# M2k_ADG_multiplexer_board.net
KiCad netlist of a schematic drawn in EAGLE
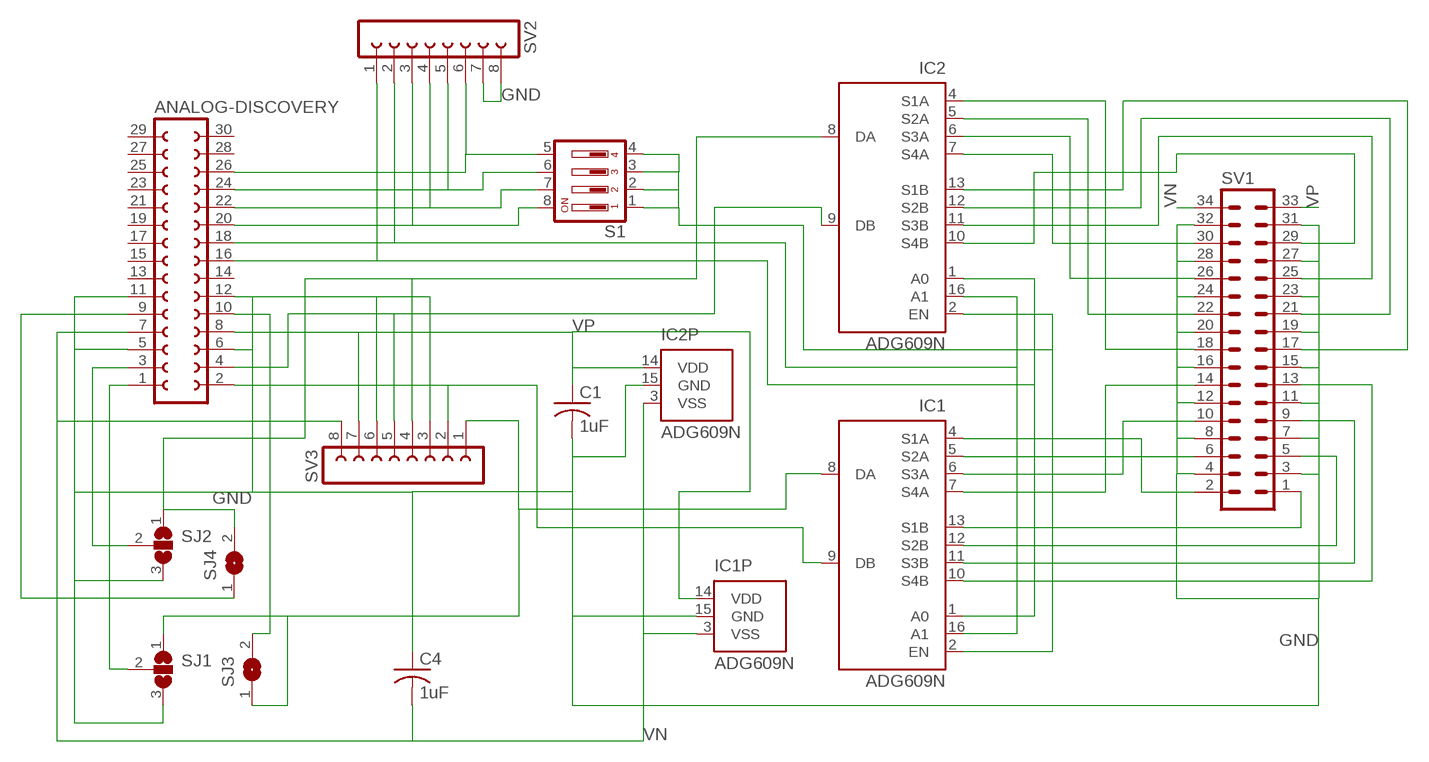
[diagram p0: schematic, sheet 1]

(export (version "E")
  (design (tool "Eeschema 10.0.6"))
  (components
    (comp (ref "ANALOG-DISCOVERY")
      (value "FE15-2")
      (footprint "eagle-import:FE15-2")
      (libsource (lib "eagle-import") (part "FE15-2"))
    )
    (comp (ref "C1")
      (value "1uF")
      (footprint "eagle-import:C050-024X044")
      (libsource (lib "eagle-import") (part "C-US050-024X044"))
    )
    (comp (ref "C4")
      (value "1uF")
      (footprint "eagle-import:C050-024X044")
      (libsource (lib "eagle-import") (part "C-US050-024X044"))
    )
    (comp (ref "IC1")
      (value "ADG609N")
      (footprint "eagle-import:DIL16")
      (fields (field (name "MF") "ALTERA CORPORATION") (field (name "MPN") "ADG609BN"))
      (libsource (lib "eagle-import") (part "ADG609N"))
    )
    (comp (ref "IC2")
      (value "ADG609N")
      (footprint "eagle-import:DIL16")
      (fields (field (name "MF") "ALTERA CORPORATION") (field (name "MPN") "ADG609BN"))
      (libsource (lib "eagle-import") (part "ADG609N"))
    )
    (comp (ref "S1")
      (value "DIP04YL")
      (footprint "eagle-import:DIP04YL")
      (libsource (lib "eagle-import") (part "DIP04YL"))
    )
    (comp (ref "SJ1")
      (value "SJ2W")
      (footprint "eagle-import:SJ_2")
      (libsource (lib "eagle-import") (part "SJ2W"))
    )
    (comp (ref "SJ2")
      (value "SJ2W")
      (footprint "eagle-import:SJ_2")
      (libsource (lib "eagle-import") (part "SJ2W"))
    )
    (comp (ref "SJ3") (value "SJ") (footprint "eagle-import:SJ") (libsource (lib "eagle-import") (part "SJ")))
    (comp (ref "SJ4") (value "SJ") (footprint "eagle-import:SJ") (libsource (lib "eagle-import") (part "SJ")))
    (comp (ref "SV1")
      (value "MA17-2")
      (footprint "eagle-import:MA17-2")
      (libsource (lib "eagle-import") (part "MA17-2"))
    )
    (comp (ref "SV2")
      (value "FE08-1")
      (footprint "eagle-import:FE08")
      (libsource (lib "eagle-import") (part "FE08-1"))
    )
    (comp (ref "SV3")
      (value "FE08-1")
      (footprint "eagle-import:FE08")
      (libsource (lib "eagle-import") (part "FE08-1"))
    )
  )
  (nets
    (net (code "1") (name "/GND") (class "Default")
      (node (ref "ANALOG-DISCOVERY") (pin "11") (pinfunction "11_11") (pintype "passive"))
      (node (ref "ANALOG-DISCOVERY") (pin "12") (pinfunction "12_12") (pintype "passive"))
      (node (ref "ANALOG-DISCOVERY") (pin "5") (pinfunction "5_5") (pintype "passive"))
      (node (ref "ANALOG-DISCOVERY") (pin "6") (pinfunction "6_6") (pintype "passive"))
      (node (ref "C1") (pin "2") (pinfunction "2_2") (pintype "passive"))
      (node (ref "C4") (pin "1") (pinfunction "1_1") (pintype "passive"))
      (node (ref "IC1") (pin "15") (pinfunction "GND_15") (pintype "power_in"))
      (node (ref "IC2") (pin "15") (pinfunction "GND_15") (pintype "power_in"))
      (node (ref "SJ1") (pin "3") (pinfunction "3_3") (pintype "passive"))
      (node (ref "SJ2") (pin "3") (pinfunction "3_3") (pintype "passive"))
      (node (ref "SV1") (pin "11") (pinfunction "11_11") (pintype "passive"))
      (node (ref "SV1") (pin "12") (pinfunction "12_12") (pintype "passive"))
      (node (ref "SV1") (pin "15") (pinfunction "15_15") (pintype "passive"))
      (node (ref "SV1") (pin "16") (pinfunction "16_16") (pintype "passive"))
      (node (ref "SV1") (pin "19") (pinfunction "19_19") (pintype "passive"))
      (node (ref "SV1") (pin "20") (pinfunction "20_20") (pintype "passive"))
      (node (ref "SV1") (pin "23") (pinfunction "23_23") (pintype "passive"))
      (node (ref "SV1") (pin "24") (pinfunction "24_24") (pintype "passive"))
      (node (ref "SV1") (pin "27") (pinfunction "27_27") (pintype "passive"))
      (node (ref "SV1") (pin "28") (pinfunction "28_28") (pintype "passive"))
      (node (ref "SV1") (pin "3") (pinfunction "3_3") (pintype "passive"))
      (node (ref "SV1") (pin "31") (pinfunction "31_31") (pintype "passive"))
      (node (ref "SV1") (pin "32") (pinfunction "32_32") (pintype "passive"))
      (node (ref "SV1") (pin "4") (pinfunction "4_4") (pintype "passive"))
      (node (ref "SV1") (pin "7") (pinfunction "7_7") (pintype "passive"))
      (node (ref "SV1") (pin "8") (pinfunction "8_8") (pintype "passive"))
      (node (ref "SV2") (pin "7") (pinfunction "7_7") (pintype "passive"))
      (node (ref "SV2") (pin "8") (pinfunction "8_8") (pintype "passive"))
      (node (ref "SV3") (pin "3") (pinfunction "3_3") (pintype "passive"))
      (node (ref "SV3") (pin "6") (pinfunction "6_6") (pintype "passive"))
    )
    (net (code "2") (name "/VN") (class "Default")
      (node (ref "ANALOG-DISCOVERY") (pin "7") (pinfunction "7_7") (pintype "passive"))
      (node (ref "C4") (pin "2") (pinfunction "2_2") (pintype "passive"))
      (node (ref "IC1") (pin "3") (pinfunction "VSS_3") (pintype "power_in"))
      (node (ref "IC2") (pin "3") (pinfunction "VSS_3") (pintype "power_in"))
      (node (ref "SV1") (pin "34") (pinfunction "34_34") (pintype "passive"))
      (node (ref "SV3") (pin "8") (pinfunction "8_8") (pintype "passive"))
    )
    (net (code "3") (name "/VP") (class "Default")
      (node (ref "ANALOG-DISCOVERY") (pin "8") (pinfunction "8_8") (pintype "passive"))
      (node (ref "C1") (pin "1") (pinfunction "1_1") (pintype "passive"))
      (node (ref "IC1") (pin "14") (pinfunction "VDD_14") (pintype "power_in"))
      (node (ref "IC2") (pin "14") (pinfunction "VDD_14") (pintype "power_in"))
      (node (ref "SV1") (pin "33") (pinfunction "33_33") (pintype "passive"))
      (node (ref "SV3") (pin "7") (pinfunction "7_7") (pintype "passive"))
    )
    (net (code "4") (name "Net-(ANALOG-DISCOVERY-Pad1)") (class "Default")
      (node (ref "ANALOG-DISCOVERY") (pin "1") (pinfunction "1_1") (pintype "passive"))
      (node (ref "SJ1") (pin "2") (pinfunction "2_2") (pintype "passive"))
    )
    (net (code "5") (name "Net-(ANALOG-DISCOVERY-Pad3)") (class "Default")
      (node (ref "ANALOG-DISCOVERY") (pin "3") (pinfunction "3_3") (pintype "passive"))
      (node (ref "SJ2") (pin "2") (pinfunction "2_2") (pintype "passive"))
    )
    (net (code "6") (name "Net-(ANALOG-DISCOVERY-Pad9)") (class "Default")
      (node (ref "ANALOG-DISCOVERY") (pin "9") (pinfunction "9_9") (pintype "passive"))
      (node (ref "SJ4") (pin "1") (pinfunction "1_1") (pintype "passive"))
    )
    (net (code "7") (name "Net-(ANALOG-DISCOVERY-Pad10)") (class "Default")
      (node (ref "ANALOG-DISCOVERY") (pin "10") (pinfunction "10_10") (pintype "passive"))
      (node (ref "SJ3") (pin "2") (pinfunction "2_2") (pintype "passive"))
    )
    (net (code "8") (name "Net-(ANALOG-DISCOVERY-Pad20)") (class "Default")
      (node (ref "ANALOG-DISCOVERY") (pin "20") (pinfunction "20_20") (pintype "passive"))
      (node (ref "S1") (pin "8") (pinfunction "8_8") (pintype "passive"))
      (node (ref "SV2") (pin "3") (pinfunction "3_3") (pintype "passive"))
    )
    (net (code "9") (name "Net-(ANALOG-DISCOVERY-Pad22)") (class "Default")
      (node (ref "ANALOG-DISCOVERY") (pin "22") (pinfunction "22_22") (pintype "passive"))
      (node (ref "S1") (pin "7") (pinfunction "7_7") (pintype "passive"))
      (node (ref "SV2") (pin "4") (pinfunction "4_4") (pintype "passive"))
    )
    (net (code "10") (name "Net-(ANALOG-DISCOVERY-Pad24)") (class "Default")
      (node (ref "ANALOG-DISCOVERY") (pin "24") (pinfunction "24_24") (pintype "passive"))
      (node (ref "S1") (pin "6") (pinfunction "6_6") (pintype "passive"))
      (node (ref "SV2") (pin "5") (pinfunction "5_5") (pintype "passive"))
    )
    (net (code "11") (name "Net-(ANALOG-DISCOVERY-Pad26)") (class "Default")
      (node (ref "ANALOG-DISCOVERY") (pin "26") (pinfunction "26_26") (pintype "passive"))
      (node (ref "S1") (pin "5") (pinfunction "5_5") (pintype "passive"))
      (node (ref "SV2") (pin "6") (pinfunction "6_6") (pintype "passive"))
    )
    (net (code "12") (name "Net-(IC1A-A0)") (class "Default")
      (node (ref "ANALOG-DISCOVERY") (pin "16") (pinfunction "16_16") (pintype "passive"))
      (node (ref "IC1") (pin "1") (pinfunction "A0_1") (pintype "input"))
      (node (ref "IC2") (pin "1") (pinfunction "A0_1") (pintype "input"))
      (node (ref "SV2") (pin "1") (pinfunction "1_1") (pintype "passive"))
    )
    (net (code "13") (name "Net-(IC1A-A1)") (class "Default")
      (node (ref "ANALOG-DISCOVERY") (pin "18") (pinfunction "18_18") (pintype "passive"))
      (node (ref "IC1") (pin "16") (pinfunction "A1_16") (pintype "input"))
      (node (ref "IC2") (pin "16") (pinfunction "A1_16") (pintype "input"))
      (node (ref "SV2") (pin "2") (pinfunction "2_2") (pintype "passive"))
    )
    (net (code "14") (name "Net-(IC1A-DA)") (class "Default")
      (node (ref "IC1") (pin "8") (pinfunction "DA_8") (pintype "bidirectional"))
      (node (ref "SJ1") (pin "1") (pinfunction "1_1") (pintype "passive"))
      (node (ref "SJ3") (pin "1") (pinfunction "1_1") (pintype "passive"))
      (node (ref "SV3") (pin "1") (pinfunction "1_1") (pintype "passive"))
    )
    (net (code "15") (name "Net-(IC1A-DB)") (class "Default")
      (node (ref "ANALOG-DISCOVERY") (pin "2") (pinfunction "2_2") (pintype "passive"))
      (node (ref "IC1") (pin "9") (pinfunction "DB_9") (pintype "bidirectional"))
      (node (ref "SV3") (pin "2") (pinfunction "2_2") (pintype "passive"))
    )
    (net (code "16") (name "Net-(IC1A-EN)") (class "Default")
      (node (ref "IC1") (pin "2") (pinfunction "EN_2") (pintype "input"))
      (node (ref "IC2") (pin "2") (pinfunction "EN_2") (pintype "input"))
      (node (ref "S1") (pin "1") (pinfunction "1_1") (pintype "passive"))
      (node (ref "S1") (pin "2") (pinfunction "2_2") (pintype "passive"))
      (node (ref "S1") (pin "3") (pinfunction "3_3") (pintype "passive"))
      (node (ref "S1") (pin "4") (pinfunction "4_4") (pintype "passive"))
    )
    (net (code "17") (name "Net-(IC1A-S1A)") (class "Default")
      (node (ref "IC1") (pin "4") (pinfunction "S1A_4") (pintype "bidirectional"))
      (node (ref "SV1") (pin "2") (pinfunction "2_2") (pintype "passive"))
    )
    (net (code "18") (name "Net-(IC1A-S1B)") (class "Default")
      (node (ref "IC1") (pin "13") (pinfunction "S1B_13") (pintype "bidirectional"))
      (node (ref "SV1") (pin "1") (pinfunction "1_1") (pintype "passive"))
    )
    (net (code "19") (name "Net-(IC1A-S2A)") (class "Default")
      (node (ref "IC1") (pin "5") (pinfunction "S2A_5") (pintype "bidirectional"))
      (node (ref "SV1") (pin "6") (pinfunction "6_6") (pintype "passive"))
    )
    (net (code "20") (name "Net-(IC1A-S2B)") (class "Default")
      (node (ref "IC1") (pin "12") (pinfunction "S2B_12") (pintype "bidirectional"))
      (node (ref "SV1") (pin "5") (pinfunction "5_5") (pintype "passive"))
    )
    (net (code "21") (name "Net-(IC1A-S3A)") (class "Default")
      (node (ref "IC1") (pin "6") (pinfunction "S3A_6") (pintype "bidirectional"))
      (node (ref "SV1") (pin "10") (pinfunction "10_10") (pintype "passive"))
    )
    (net (code "22") (name "Net-(IC1A-S3B)") (class "Default")
      (node (ref "IC1") (pin "11") (pinfunction "S3B_11") (pintype "bidirectional"))
      (node (ref "SV1") (pin "9") (pinfunction "9_9") (pintype "passive"))
    )
    (net (code "23") (name "Net-(IC1A-S4A)") (class "Default")
      (node (ref "IC1") (pin "7") (pinfunction "S4A_7") (pintype "bidirectional"))
      (node (ref "SV1") (pin "14") (pinfunction "14_14") (pintype "passive"))
    )
    (net (code "24") (name "Net-(IC1A-S4B)") (class "Default")
      (node (ref "IC1") (pin "10") (pinfunction "S4B_10") (pintype "bidirectional"))
      (node (ref "SV1") (pin "13") (pinfunction "13_13") (pintype "passive"))
    )
    (net (code "25") (name "Net-(IC2A-DA)") (class "Default")
      (node (ref "IC2") (pin "8") (pinfunction "DA_8") (pintype "bidirectional"))
      (node (ref "SJ2") (pin "1") (pinfunction "1_1") (pintype "passive"))
      (node (ref "SJ4") (pin "2") (pinfunction "2_2") (pintype "passive"))
      (node (ref "SV3") (pin "4") (pinfunction "4_4") (pintype "passive"))
    )
    (net (code "26") (name "Net-(IC2A-DB)") (class "Default")
      (node (ref "ANALOG-DISCOVERY") (pin "4") (pinfunction "4_4") (pintype "passive"))
      (node (ref "IC2") (pin "9") (pinfunction "DB_9") (pintype "bidirectional"))
      (node (ref "SV3") (pin "5") (pinfunction "5_5") (pintype "passive"))
    )
    (net (code "27") (name "Net-(IC2A-S1A)") (class "Default")
      (node (ref "IC2") (pin "4") (pinfunction "S1A_4") (pintype "bidirectional"))
      (node (ref "SV1") (pin "18") (pinfunction "18_18") (pintype "passive"))
    )
    (net (code "28") (name "Net-(IC2A-S1B)") (class "Default")
      (node (ref "IC2") (pin "13") (pinfunction "S1B_13") (pintype "bidirectional"))
      (node (ref "SV1") (pin "17") (pinfunction "17_17") (pintype "passive"))
    )
    (net (code "29") (name "Net-(IC2A-S2A)") (class "Default")
      (node (ref "IC2") (pin "5") (pinfunction "S2A_5") (pintype "bidirectional"))
      (node (ref "SV1") (pin "22") (pinfunction "22_22") (pintype "passive"))
    )
    (net (code "30") (name "Net-(IC2A-S2B)") (class "Default")
      (node (ref "IC2") (pin "12") (pinfunction "S2B_12") (pintype "bidirectional"))
      (node (ref "SV1") (pin "21") (pinfunction "21_21") (pintype "passive"))
    )
    (net (code "31") (name "Net-(IC2A-S3A)") (class "Default")
      (node (ref "IC2") (pin "6") (pinfunction "S3A_6") (pintype "bidirectional"))
      (node (ref "SV1") (pin "26") (pinfunction "26_26") (pintype "passive"))
    )
    (net (code "32") (name "Net-(IC2A-S3B)") (class "Default")
      (node (ref "IC2") (pin "11") (pinfunction "S3B_11") (pintype "bidirectional"))
      (node (ref "SV1") (pin "25") (pinfunction "25_25") (pintype "passive"))
    )
    (net (code "33") (name "Net-(IC2A-S4A)") (class "Default")
      (node (ref "IC2") (pin "7") (pinfunction "S4A_7") (pintype "bidirectional"))
      (node (ref "SV1") (pin "30") (pinfunction "30_30") (pintype "passive"))
    )
    (net (code "34") (name "Net-(IC2A-S4B)") (class "Default")
      (node (ref "IC2") (pin "10") (pinfunction "S4B_10") (pintype "bidirectional"))
      (node (ref "SV1") (pin "29") (pinfunction "29_29") (pintype "passive"))
    )
    (net (code "35") (name "unconnected-(ANALOG-DISCOVERY-Pad13)") (class "Default")
      (node (ref "ANALOG-DISCOVERY") (pin "13") (pinfunction "13_13") (pintype "passive"))
    )
    (net (code "36") (name "unconnected-(ANALOG-DISCOVERY-Pad14)") (class "Default")
      (node (ref "ANALOG-DISCOVERY") (pin "14") (pinfunction "14_14") (pintype "passive"))
    )
    (net (code "37") (name "unconnected-(ANALOG-DISCOVERY-Pad15)") (class "Default")
      (node (ref "ANALOG-DISCOVERY") (pin "15") (pinfunction "15_15") (pintype "passive"))
    )
    (net (code "38") (name "unconnected-(ANALOG-DISCOVERY-Pad17)") (class "Default")
      (node (ref "ANALOG-DISCOVERY") (pin "17") (pinfunction "17_17") (pintype "passive"))
    )
    (net (code "39") (name "unconnected-(ANALOG-DISCOVERY-Pad19)") (class "Default")
      (node (ref "ANALOG-DISCOVERY") (pin "19") (pinfunction "19_19") (pintype "passive"))
    )
    (net (code "40") (name "unconnected-(ANALOG-DISCOVERY-Pad21)") (class "Default")
      (node (ref "ANALOG-DISCOVERY") (pin "21") (pinfunction "21_21") (pintype "passive"))
    )
    (net (code "41") (name "unconnected-(ANALOG-DISCOVERY-Pad23)") (class "Default")
      (node (ref "ANALOG-DISCOVERY") (pin "23") (pinfunction "23_23") (pintype "passive"))
    )
    (net (code "42") (name "unconnected-(ANALOG-DISCOVERY-Pad25)") (class "Default")
      (node (ref "ANALOG-DISCOVERY") (pin "25") (pinfunction "25_25") (pintype "passive"))
    )
    (net (code "43") (name "unconnected-(ANALOG-DISCOVERY-Pad27)") (class "Default")
      (node (ref "ANALOG-DISCOVERY") (pin "27") (pinfunction "27_27") (pintype "passive"))
    )
    (net (code "44") (name "unconnected-(ANALOG-DISCOVERY-Pad28)") (class "Default")
      (node (ref "ANALOG-DISCOVERY") (pin "28") (pinfunction "28_28") (pintype "passive"))
    )
    (net (code "45") (name "unconnected-(ANALOG-DISCOVERY-Pad29)") (class "Default")
      (node (ref "ANALOG-DISCOVERY") (pin "29") (pinfunction "29_29") (pintype "passive"))
    )
    (net (code "46") (name "unconnected-(ANALOG-DISCOVERY-Pad30)") (class "Default")
      (node (ref "ANALOG-DISCOVERY") (pin "30") (pinfunction "30_30") (pintype "passive"))
    )
  )
)
